# 1P3W_v1p0.net
KiCad netlist of a schematic drawn in EAGLE
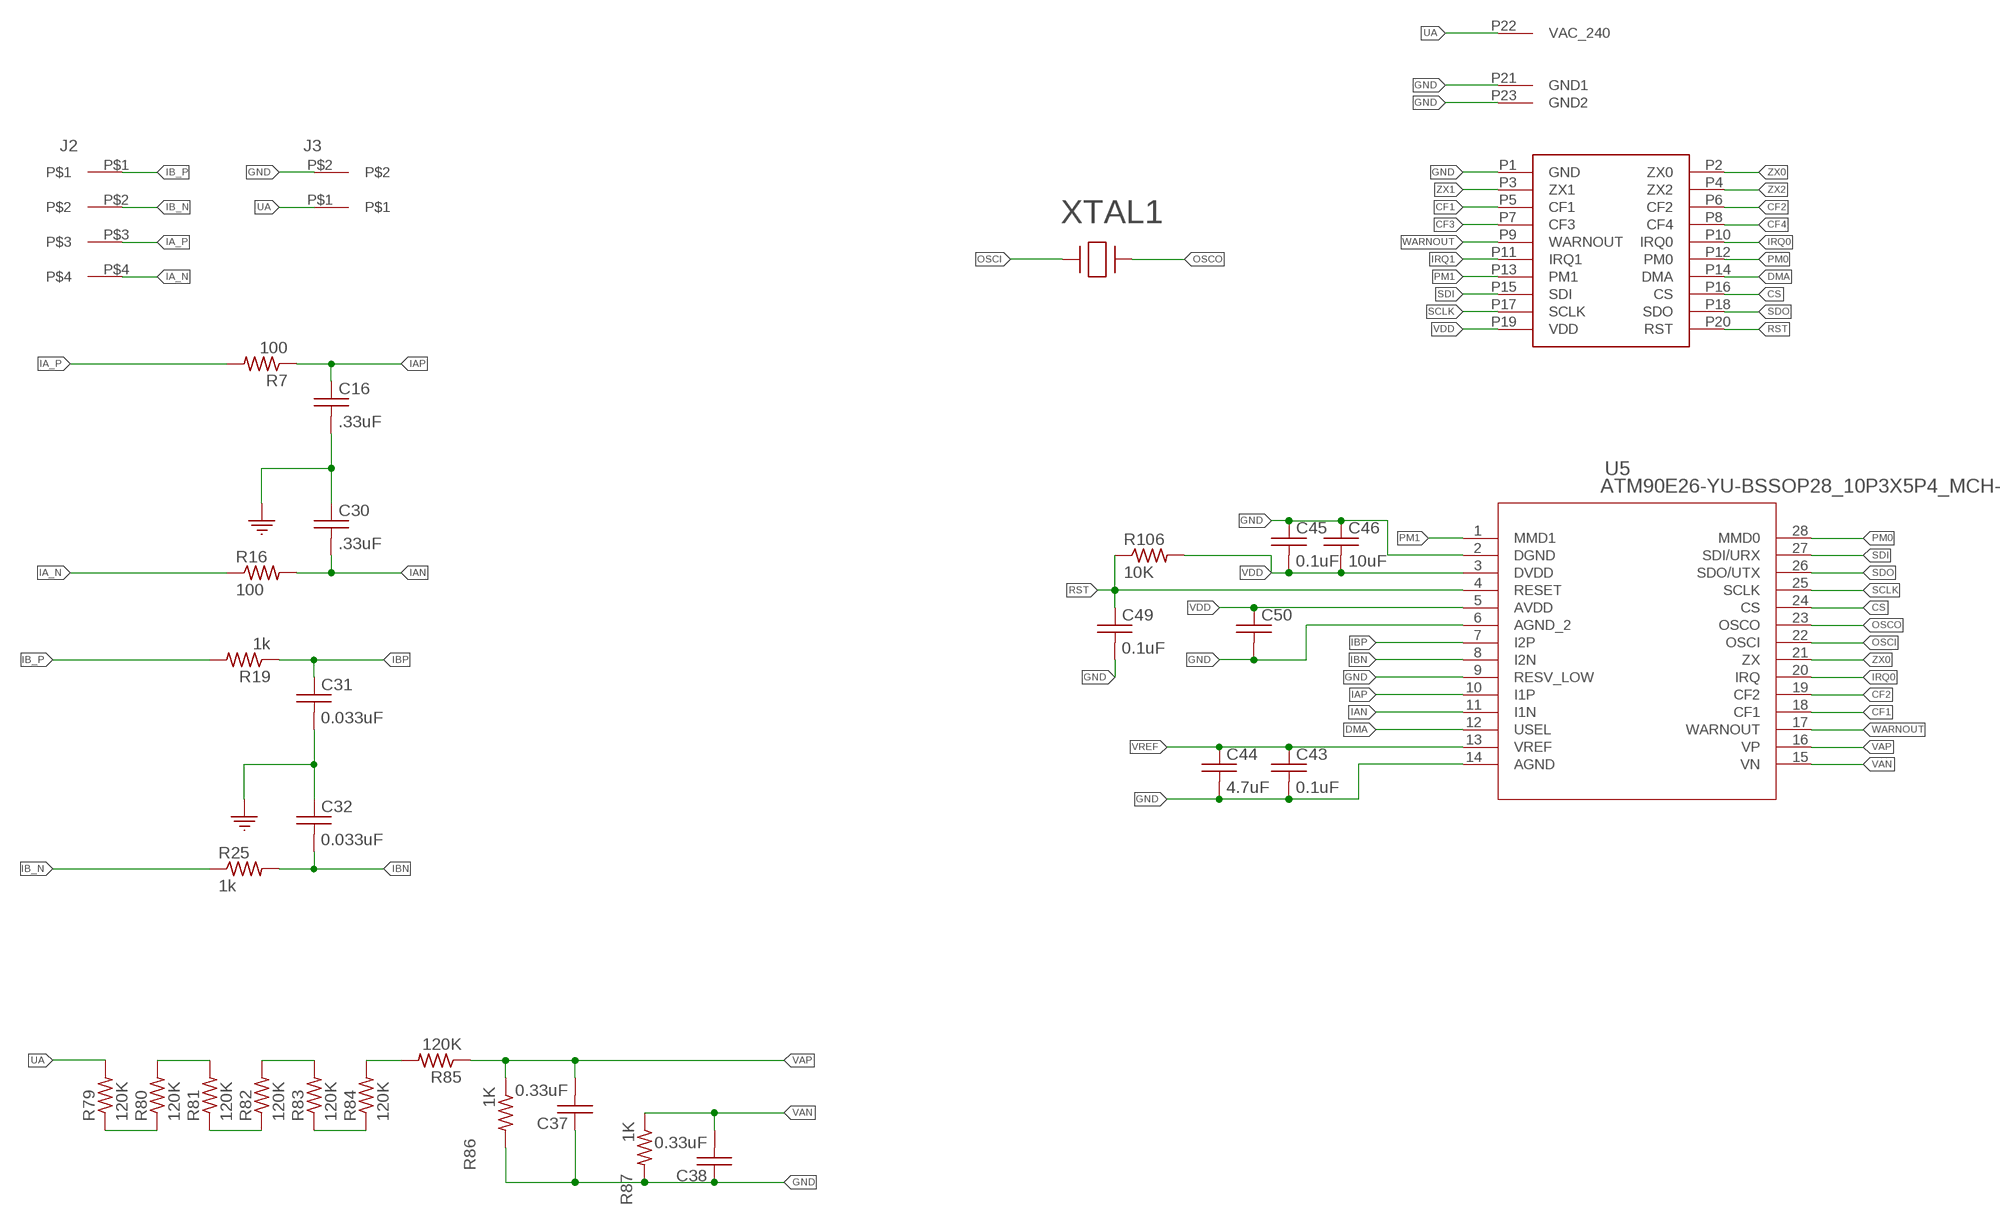
[diagram p0: schematic, sheet 1]

(export (version "E")
  (design (tool "Eeschema 10.0.6"))
  (components
    (comp (ref "C16")
      (value ".33uF")
      (footprint "eagle-import:0402")
      (libsource (lib "eagle-import") (part "C_0402"))
    )
    (comp (ref "C30")
      (value ".33uF")
      (footprint "eagle-import:0402")
      (libsource (lib "eagle-import") (part "C_0402"))
    )
    (comp (ref "C31")
      (value "0.033uF")
      (footprint "eagle-import:0402")
      (libsource (lib "eagle-import") (part "C_0402"))
    )
    (comp (ref "C32")
      (value "0.033uF")
      (footprint "eagle-import:0402")
      (libsource (lib "eagle-import") (part "C_0402"))
    )
    (comp (ref "C37")
      (value "0.33uF")
      (footprint "eagle-import:0402")
      (libsource (lib "eagle-import") (part "C_0402"))
    )
    (comp (ref "C38")
      (value "0.33uF")
      (footprint "eagle-import:0402")
      (libsource (lib "eagle-import") (part "C_0402"))
    )
    (comp (ref "C43")
      (value "0.1uF")
      (footprint "eagle-import:0402")
      (libsource (lib "eagle-import") (part "C_0402"))
    )
    (comp (ref "C44")
      (value "4.7uF")
      (footprint "eagle-import:0402")
      (libsource (lib "eagle-import") (part "C_0402"))
    )
    (comp (ref "C45")
      (value "0.1uF")
      (footprint "eagle-import:0402")
      (libsource (lib "eagle-import") (part "C_0402"))
    )
    (comp (ref "C46")
      (value "10uF")
      (footprint "eagle-import:0402")
      (libsource (lib "eagle-import") (part "C_0402"))
    )
    (comp (ref "C49")
      (value "0.1uF")
      (footprint "eagle-import:0402")
      (libsource (lib "eagle-import") (part "C_0402"))
    )
    (comp (ref "C50")
      (value "C_0402")
      (footprint "eagle-import:0402")
      (libsource (lib "eagle-import") (part "C_0402"))
    )
    (comp (ref "J2")
      (value "3.81MM_1_X_4_RT_ANGLE_PLUG_HEADER")
      (footprint "eagle-import:1X4_3.81MM_PITCH")
      (libsource (lib "eagle-import") (part "3.81MM_1_X_4_RT_ANGLE_PLUG_HEADER"))
    )
    (comp (ref "J3")
      (value "3.81MM_1_X_2_RT_ANGLE_PLUG_HEADER")
      (footprint "eagle-import:2_3.81MM_PITCH")
      (libsource (lib "eagle-import") (part "3.81MM_1_X_2_RT_ANGLE_PLUG_HEADER"))
    )
    (comp (ref "R7")
      (value "100")
      (footprint "eagle-import:0402")
      (libsource (lib "eagle-import") (part "R_0402"))
    )
    (comp (ref "R16")
      (value "100")
      (footprint "eagle-import:0402")
      (libsource (lib "eagle-import") (part "R_0402"))
    )
    (comp (ref "R19")
      (value "1k")
      (footprint "eagle-import:0402")
      (libsource (lib "eagle-import") (part "R_0402"))
    )
    (comp (ref "R25")
      (value "1k")
      (footprint "eagle-import:0402")
      (libsource (lib "eagle-import") (part "R_0402"))
    )
    (comp (ref "R79")
      (value "120K")
      (footprint "eagle-import:0402")
      (libsource (lib "eagle-import") (part "R_0402"))
    )
    (comp (ref "R80")
      (value "120K")
      (footprint "eagle-import:0402")
      (libsource (lib "eagle-import") (part "R_0402"))
    )
    (comp (ref "R81")
      (value "120K")
      (footprint "eagle-import:0402")
      (libsource (lib "eagle-import") (part "R_0402"))
    )
    (comp (ref "R82")
      (value "120K")
      (footprint "eagle-import:0402")
      (libsource (lib "eagle-import") (part "R_0402"))
    )
    (comp (ref "R83")
      (value "120K")
      (footprint "eagle-import:0402")
      (libsource (lib "eagle-import") (part "R_0402"))
    )
    (comp (ref "R84")
      (value "120K")
      (footprint "eagle-import:0402")
      (libsource (lib "eagle-import") (part "R_0402"))
    )
    (comp (ref "R85")
      (value "120K")
      (footprint "eagle-import:0402")
      (libsource (lib "eagle-import") (part "R_0402"))
    )
    (comp (ref "R86")
      (value "1K")
      (footprint "eagle-import:0402")
      (libsource (lib "eagle-import") (part "R_0402"))
    )
    (comp (ref "R87")
      (value "1K")
      (footprint "eagle-import:0402")
      (libsource (lib "eagle-import") (part "R_0402"))
    )
    (comp (ref "R106")
      (value "10K")
      (footprint "eagle-import:0402")
      (libsource (lib "eagle-import") (part "R_0402"))
    )
    (comp (ref "U$1")
      (value "METER_BASE")
      (footprint "eagle-import:METER_BASE")
      (libsource (lib "eagle-import") (part "METER_BASE"))
    )
    (comp (ref "U5")
      (value "ATM90E26-YU-BSSOP28_10P3X5P4_MCH-M")
      (footprint "eagle-import:SSOP28_10P3X5P4_MCH-M")
      (fields
        (field (name "MANUFACTURER_PART_NUMBER") "ATM90E26-YU-B")
        (field (name "COPYRIGHT") "Copyright (C) 2018 Accelerated Designs. All rights reserved")
      )
      (libsource (lib "eagle-import") (part "ATM90E26-YU-BSSOP28_10P3X5P4_MCH-M"))
    )
    (comp (ref "XTAL1")
      (value "ABLS-8.192MHZ-B2-TXTAL_HC/49US_ABLS_ABR-M")
      (footprint "eagle-import:XTAL_HC_49US_ABLS_ABR-M")
      (fields
        (field (name "MANUFACTURER_PART_NUMBER") "ABLS-8.192MHZ-B2-T")
        (field (name "COPYRIGHT") "Copyright (C) 2018 Accelerated Designs. All rights reserved")
      )
      (libsource (lib "eagle-import") (part "ABLS-8.192MHZ-B2-TXTAL_HC/49US_ABLS_ABR-M"))
    )
  )
  (nets
    (net (code "1") (name "CF1") (class "Default")
      (node (ref "U$1") (pin "P5") (pinfunction "CF1_P5") (pintype "bidirectional"))
      (node (ref "U5") (pin "18") (pinfunction "CF1_18") (pintype "bidirectional"))
    )
    (net (code "2") (name "CF2") (class "Default")
      (node (ref "U$1") (pin "P6") (pinfunction "CF2_P6") (pintype "bidirectional"))
      (node (ref "U5") (pin "19") (pinfunction "CF2_19") (pintype "bidirectional"))
    )
    (net (code "3") (name "CF3") (class "Default")
      (node (ref "U$1") (pin "P7") (pinfunction "CF3_P7") (pintype "bidirectional"))
    )
    (net (code "4") (name "CF4") (class "Default")
      (node (ref "U$1") (pin "P8") (pinfunction "CF4_P8") (pintype "bidirectional"))
    )
    (net (code "5") (name "CS") (class "Default")
      (node (ref "U$1") (pin "P16") (pinfunction "CS_P16") (pintype "bidirectional"))
      (node (ref "U5") (pin "24") (pinfunction "CS_24") (pintype "passive"))
    )
    (net (code "6") (name "DMA") (class "Default")
      (node (ref "U$1") (pin "P14") (pinfunction "DMA_P14") (pintype "bidirectional"))
      (node (ref "U5") (pin "12") (pinfunction "USEL_12") (pintype "passive"))
    )
    (net (code "7") (name "GND") (class "Default")
      (node (ref "C16") (pin "P$2") (pinfunction "2_P$2") (pintype "passive"))
      (node (ref "C30") (pin "P$1") (pinfunction "1_P$1") (pintype "passive"))
      (node (ref "C31") (pin "P$2") (pinfunction "2_P$2") (pintype "passive"))
      (node (ref "C32") (pin "P$1") (pinfunction "1_P$1") (pintype "passive"))
      (node (ref "C37") (pin "P$1") (pinfunction "1_P$1") (pintype "passive"))
      (node (ref "C38") (pin "P$1") (pinfunction "1_P$1") (pintype "passive"))
      (node (ref "C43") (pin "P$2") (pinfunction "2_P$2") (pintype "passive"))
      (node (ref "C44") (pin "P$2") (pinfunction "2_P$2") (pintype "passive"))
      (node (ref "C45") (pin "P$1") (pinfunction "1_P$1") (pintype "passive"))
      (node (ref "C46") (pin "P$1") (pinfunction "1_P$1") (pintype "passive"))
      (node (ref "C49") (pin "P$2") (pinfunction "2_P$2") (pintype "passive"))
      (node (ref "C50") (pin "P$2") (pinfunction "2_P$2") (pintype "passive"))
      (node (ref "J3") (pin "P$2") (pinfunction "P$2_P$2") (pintype "bidirectional"))
      (node (ref "R86") (pin "P$2") (pinfunction "2_P$2") (pintype "passive"))
      (node (ref "R87") (pin "P$2") (pinfunction "2_P$2") (pintype "passive"))
      (node (ref "U$1") (pin "P1") (pinfunction "GND_P1") (pintype "bidirectional"))
      (node (ref "U$1") (pin "P21") (pinfunction "GND1_P21") (pintype "bidirectional"))
      (node (ref "U$1") (pin "P23") (pinfunction "GND2_P23") (pintype "bidirectional"))
      (node (ref "U5") (pin "14") (pinfunction "AGND_14") (pintype "passive"))
      (node (ref "U5") (pin "2") (pinfunction "DGND_2") (pintype "passive"))
      (node (ref "U5") (pin "6") (pinfunction "AGND_2_6") (pintype "passive"))
      (node (ref "U5") (pin "9") (pinfunction "RESV_LOW_9") (pintype "passive"))
    )
    (net (code "8") (name "IAN") (class "Default")
      (node (ref "C30") (pin "P$2") (pinfunction "2_P$2") (pintype "passive"))
      (node (ref "R16") (pin "P$2") (pinfunction "2_P$2") (pintype "passive"))
      (node (ref "U5") (pin "11") (pinfunction "I1N_11") (pintype "bidirectional"))
    )
    (net (code "9") (name "IAP") (class "Default")
      (node (ref "C16") (pin "P$1") (pinfunction "1_P$1") (pintype "passive"))
      (node (ref "R7") (pin "P$1") (pinfunction "1_P$1") (pintype "passive"))
      (node (ref "U5") (pin "10") (pinfunction "I1P_10") (pintype "bidirectional"))
    )
    (net (code "10") (name "IA_N") (class "Default")
      (node (ref "J2") (pin "P$4") (pinfunction "P$4_P$4") (pintype "bidirectional"))
      (node (ref "R16") (pin "P$1") (pinfunction "1_P$1") (pintype "passive"))
    )
    (net (code "11") (name "IA_P") (class "Default")
      (node (ref "J2") (pin "P$3") (pinfunction "P$3_P$3") (pintype "bidirectional"))
      (node (ref "R7") (pin "P$2") (pinfunction "2_P$2") (pintype "passive"))
    )
    (net (code "12") (name "IBN") (class "Default")
      (node (ref "C32") (pin "P$2") (pinfunction "2_P$2") (pintype "passive"))
      (node (ref "R25") (pin "P$2") (pinfunction "2_P$2") (pintype "passive"))
      (node (ref "U5") (pin "8") (pinfunction "I2N_8") (pintype "bidirectional"))
    )
    (net (code "13") (name "IBP") (class "Default")
      (node (ref "C31") (pin "P$1") (pinfunction "1_P$1") (pintype "passive"))
      (node (ref "R19") (pin "P$1") (pinfunction "1_P$1") (pintype "passive"))
      (node (ref "U5") (pin "7") (pinfunction "I2P_7") (pintype "bidirectional"))
    )
    (net (code "14") (name "IB_N") (class "Default")
      (node (ref "J2") (pin "P$2") (pinfunction "P$2_P$2") (pintype "bidirectional"))
      (node (ref "R25") (pin "P$1") (pinfunction "1_P$1") (pintype "passive"))
    )
    (net (code "15") (name "IB_P") (class "Default")
      (node (ref "J2") (pin "P$1") (pinfunction "P$1_P$1") (pintype "bidirectional"))
      (node (ref "R19") (pin "P$2") (pinfunction "2_P$2") (pintype "passive"))
    )
    (net (code "16") (name "IRQ0") (class "Default")
      (node (ref "U$1") (pin "P10") (pinfunction "IRQ0_P10") (pintype "bidirectional"))
      (node (ref "U5") (pin "20") (pinfunction "IRQ_20") (pintype "passive"))
    )
    (net (code "17") (name "IRQ1") (class "Default")
      (node (ref "U$1") (pin "P11") (pinfunction "IRQ1_P11") (pintype "bidirectional"))
    )
    (net (code "18") (name "Net-(R79-1)") (class "Default")
      (node (ref "R79") (pin "P$1") (pinfunction "1_P$1") (pintype "passive"))
      (node (ref "R80") (pin "P$1") (pinfunction "1_P$1") (pintype "passive"))
    )
    (net (code "19") (name "Net-(R80-2)") (class "Default")
      (node (ref "R80") (pin "P$2") (pinfunction "2_P$2") (pintype "passive"))
      (node (ref "R81") (pin "P$2") (pinfunction "2_P$2") (pintype "passive"))
    )
    (net (code "20") (name "Net-(R81-1)") (class "Default")
      (node (ref "R81") (pin "P$1") (pinfunction "1_P$1") (pintype "passive"))
      (node (ref "R82") (pin "P$1") (pinfunction "1_P$1") (pintype "passive"))
    )
    (net (code "21") (name "Net-(R82-2)") (class "Default")
      (node (ref "R82") (pin "P$2") (pinfunction "2_P$2") (pintype "passive"))
      (node (ref "R83") (pin "P$2") (pinfunction "2_P$2") (pintype "passive"))
    )
    (net (code "22") (name "Net-(R83-1)") (class "Default")
      (node (ref "R83") (pin "P$1") (pinfunction "1_P$1") (pintype "passive"))
      (node (ref "R84") (pin "P$1") (pinfunction "1_P$1") (pintype "passive"))
    )
    (net (code "23") (name "Net-(R84-2)") (class "Default")
      (node (ref "R84") (pin "P$2") (pinfunction "2_P$2") (pintype "passive"))
      (node (ref "R85") (pin "P$2") (pinfunction "2_P$2") (pintype "passive"))
    )
    (net (code "24") (name "OSCI") (class "Default")
      (node (ref "U5") (pin "22") (pinfunction "OSCI_22") (pintype "passive"))
      (node (ref "XTAL1") (pin "1") (pinfunction "1_1") (pintype "passive"))
    )
    (net (code "25") (name "OSCO") (class "Default")
      (node (ref "U5") (pin "23") (pinfunction "OSCO_23") (pintype "passive"))
      (node (ref "XTAL1") (pin "2") (pinfunction "2_2") (pintype "passive"))
    )
    (net (code "26") (name "PM0") (class "Default")
      (node (ref "U$1") (pin "P12") (pinfunction "PM0_P12") (pintype "bidirectional"))
      (node (ref "U5") (pin "28") (pinfunction "MMD0_28") (pintype "bidirectional"))
    )
    (net (code "27") (name "PM1") (class "Default")
      (node (ref "U$1") (pin "P13") (pinfunction "PM1_P13") (pintype "bidirectional"))
      (node (ref "U5") (pin "1") (pinfunction "MMD1_1") (pintype "bidirectional"))
    )
    (net (code "28") (name "RST") (class "Default")
      (node (ref "C49") (pin "P$1") (pinfunction "1_P$1") (pintype "passive"))
      (node (ref "R106") (pin "P$1") (pinfunction "1_P$1") (pintype "passive"))
      (node (ref "U$1") (pin "P20") (pinfunction "RST_P20") (pintype "bidirectional"))
      (node (ref "U5") (pin "4") (pinfunction "RESET_4") (pintype "passive"))
    )
    (net (code "29") (name "SCLK") (class "Default")
      (node (ref "U$1") (pin "P17") (pinfunction "SCLK_P17") (pintype "bidirectional"))
      (node (ref "U5") (pin "25") (pinfunction "SCLK_25") (pintype "passive"))
    )
    (net (code "30") (name "SDI") (class "Default")
      (node (ref "U$1") (pin "P15") (pinfunction "SDI_P15") (pintype "bidirectional"))
      (node (ref "U5") (pin "27") (pinfunction "SDI/URX_27") (pintype "passive"))
    )
    (net (code "31") (name "SDO") (class "Default")
      (node (ref "U$1") (pin "P18") (pinfunction "SDO_P18") (pintype "bidirectional"))
      (node (ref "U5") (pin "26") (pinfunction "SDO/UTX_26") (pintype "passive"))
    )
    (net (code "32") (name "UA") (class "Default")
      (node (ref "J3") (pin "P$1") (pinfunction "P$1_P$1") (pintype "bidirectional"))
      (node (ref "R79") (pin "P$2") (pinfunction "2_P$2") (pintype "passive"))
      (node (ref "U$1") (pin "P22") (pinfunction "VAC_240_P22") (pintype "bidirectional"))
    )
    (net (code "33") (name "VAN") (class "Default")
      (node (ref "C38") (pin "P$2") (pinfunction "2_P$2") (pintype "passive"))
      (node (ref "R87") (pin "P$1") (pinfunction "1_P$1") (pintype "passive"))
      (node (ref "U5") (pin "15") (pinfunction "VN_15") (pintype "passive"))
    )
    (net (code "34") (name "VAP") (class "Default")
      (node (ref "C37") (pin "P$2") (pinfunction "2_P$2") (pintype "passive"))
      (node (ref "R85") (pin "P$1") (pinfunction "1_P$1") (pintype "passive"))
      (node (ref "R86") (pin "P$1") (pinfunction "1_P$1") (pintype "passive"))
      (node (ref "U5") (pin "16") (pinfunction "VP_16") (pintype "passive"))
    )
    (net (code "35") (name "VDD") (class "Default")
      (node (ref "C45") (pin "P$2") (pinfunction "2_P$2") (pintype "passive"))
      (node (ref "C46") (pin "P$2") (pinfunction "2_P$2") (pintype "passive"))
      (node (ref "C50") (pin "P$1") (pinfunction "1_P$1") (pintype "passive"))
      (node (ref "R106") (pin "P$2") (pinfunction "2_P$2") (pintype "passive"))
      (node (ref "U$1") (pin "P19") (pinfunction "VDD_P19") (pintype "bidirectional"))
      (node (ref "U5") (pin "3") (pinfunction "DVDD_3") (pintype "power_in"))
      (node (ref "U5") (pin "5") (pinfunction "AVDD_5") (pintype "power_in"))
    )
    (net (code "36") (name "VREF") (class "Default")
      (node (ref "C43") (pin "P$1") (pinfunction "1_P$1") (pintype "passive"))
      (node (ref "C44") (pin "P$1") (pinfunction "1_P$1") (pintype "passive"))
      (node (ref "U5") (pin "13") (pinfunction "VREF_13") (pintype "power_in"))
    )
    (net (code "37") (name "WARNOUT") (class "Default")
      (node (ref "U$1") (pin "P9") (pinfunction "WARNOUT_P9") (pintype "bidirectional"))
      (node (ref "U5") (pin "17") (pinfunction "WARNOUT_17") (pintype "output"))
    )
    (net (code "38") (name "ZX0") (class "Default")
      (node (ref "U$1") (pin "P2") (pinfunction "ZX0_P2") (pintype "bidirectional"))
      (node (ref "U5") (pin "21") (pinfunction "ZX_21") (pintype "passive"))
    )
    (net (code "39") (name "ZX1") (class "Default")
      (node (ref "U$1") (pin "P3") (pinfunction "ZX1_P3") (pintype "bidirectional"))
    )
    (net (code "40") (name "ZX2") (class "Default")
      (node (ref "U$1") (pin "P4") (pinfunction "ZX2_P4") (pintype "bidirectional"))
    )
  )
)
